# RelayCard_LED_Monitor.net
KiCad netlist of a schematic drawn in Altium Designer
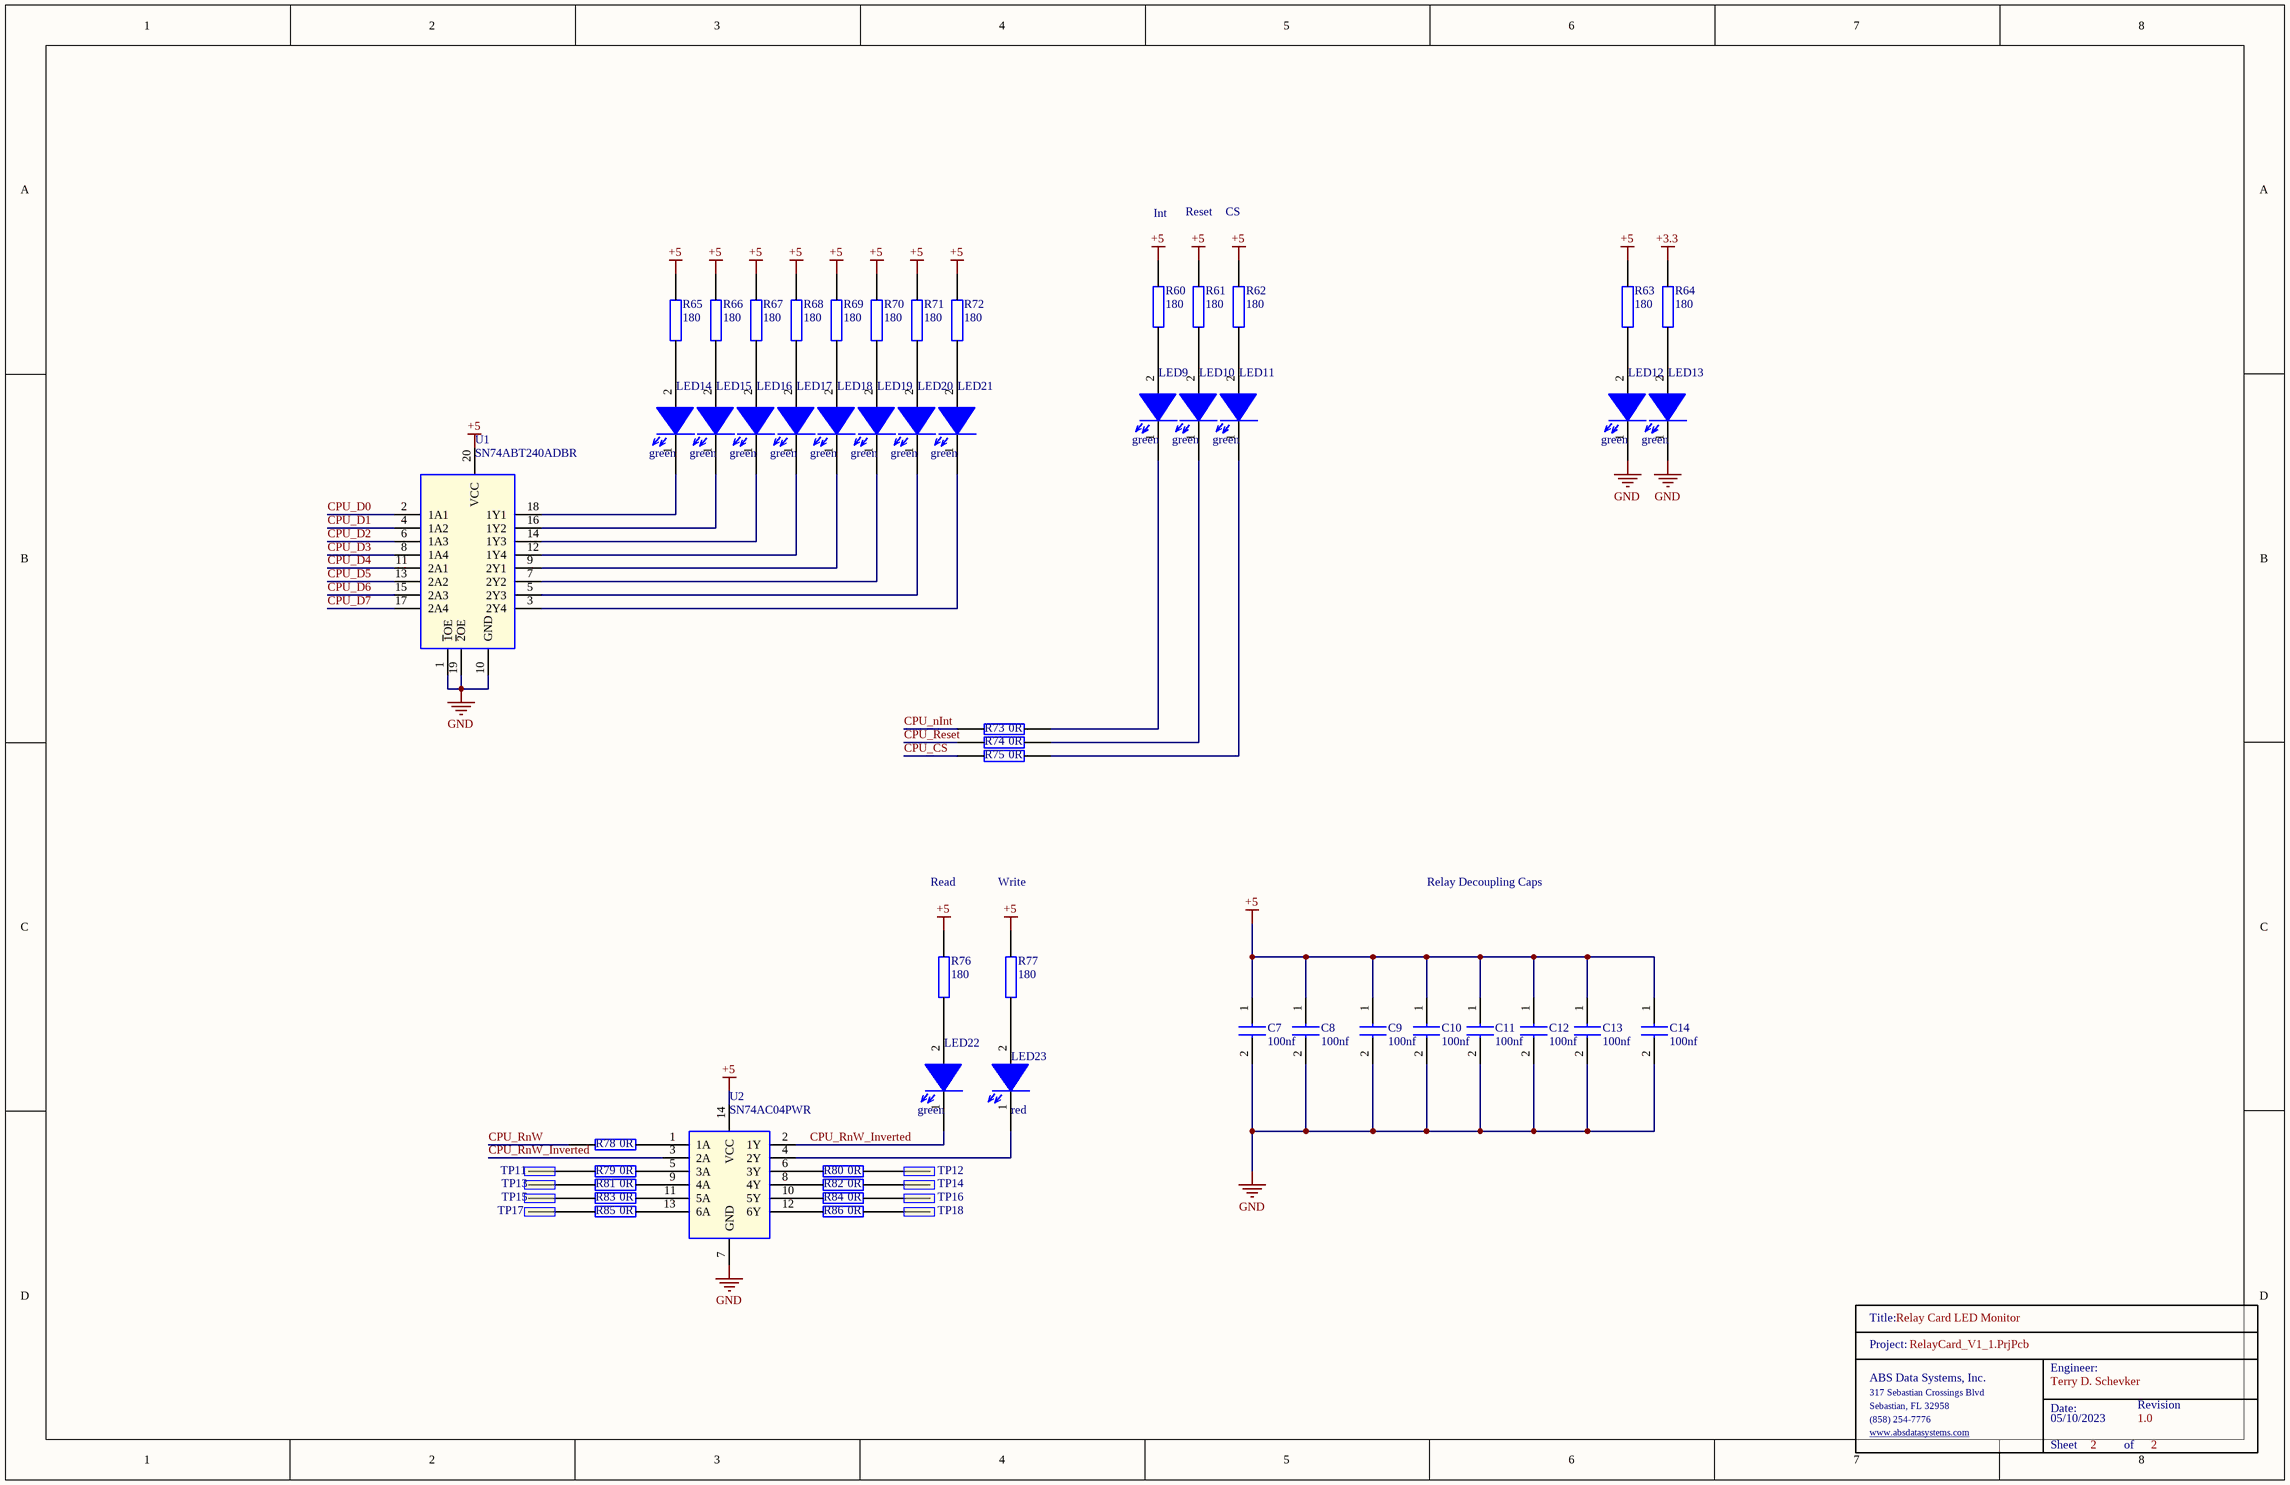
[diagram p0: RelayCard_LED_Monitor.SchDoc]

(export (version "E")
  (design (tool "Eeschema 10.0.6"))
  (components
    (comp (ref "C7")
      (value "100nf")
      (footprint "0603")
      (description "Samsung Electro-Mechanics 0603 100nf")
      (libsource (lib "Capacitors") (part "CL10B104JB8NNNC"))
    )
    (comp (ref "C8")
      (value "100nf")
      (footprint "0603")
      (description "Samsung Electro-Mechanics 0603 100nf")
      (libsource (lib "Capacitors") (part "CL10B104JB8NNNC"))
    )
    (comp (ref "C9")
      (value "100nf")
      (footprint "0603")
      (description "Samsung Electro-Mechanics 0603 100nf")
      (libsource (lib "Capacitors") (part "CL10B104JB8NNNC"))
    )
    (comp (ref "C10")
      (value "100nf")
      (footprint "0603")
      (description "Samsung Electro-Mechanics 0603 100nf")
      (libsource (lib "Capacitors") (part "CL10B104JB8NNNC"))
    )
    (comp (ref "C11")
      (value "100nf")
      (footprint "0603")
      (description "Samsung Electro-Mechanics 0603 100nf")
      (libsource (lib "Capacitors") (part "CL10B104JB8NNNC"))
    )
    (comp (ref "C12")
      (value "100nf")
      (footprint "0603")
      (description "Samsung Electro-Mechanics 0603 100nf")
      (libsource (lib "Capacitors") (part "CL10B104JB8NNNC"))
    )
    (comp (ref "C13")
      (value "100nf")
      (footprint "0603")
      (description "Samsung Electro-Mechanics 0603 100nf")
      (libsource (lib "Capacitors") (part "CL10B104JB8NNNC"))
    )
    (comp (ref "C14")
      (value "100nf")
      (footprint "0603")
      (description "Samsung Electro-Mechanics 0603 100nf")
      (libsource (lib "Capacitors") (part "CL10B104JB8NNNC"))
    )
    (comp (ref "LED9")
      (value "green")
      (footprint "0603_Diode")
      (description "Wurth Elektronik 0603 green")
      (fields
        (field (name "MANUFACTURER") "Wurth Electronics")
        (field (name "MANUFACTURER PART NUMBER") "150060GS75000")
      )
      (libsource (lib "Misc") (part "150060GS75000"))
    )
    (comp (ref "LED10")
      (value "green")
      (footprint "0603_Diode")
      (description "Wurth Elektronik 0603 green")
      (fields
        (field (name "MANUFACTURER") "Wurth Electronics")
        (field (name "MANUFACTURER PART NUMBER") "150060GS75000")
      )
      (libsource (lib "Misc") (part "150060GS75000"))
    )
    (comp (ref "LED11")
      (value "green")
      (footprint "0603_Diode")
      (description "Wurth Elektronik 0603 green")
      (fields
        (field (name "MANUFACTURER") "Wurth Electronics")
        (field (name "MANUFACTURER PART NUMBER") "150060GS75000")
      )
      (libsource (lib "Misc") (part "150060GS75000"))
    )
    (comp (ref "LED12")
      (value "green")
      (footprint "0603_Diode")
      (description "Wurth Elektronik 0603 green")
      (fields
        (field (name "MANUFACTURER") "Wurth Electronics")
        (field (name "MANUFACTURER PART NUMBER") "150060GS75000")
      )
      (libsource (lib "Misc") (part "150060GS75000"))
    )
    (comp (ref "LED13")
      (value "green")
      (footprint "0603_Diode")
      (description "Wurth Elektronik 0603 green")
      (fields
        (field (name "MANUFACTURER") "Wurth Electronics")
        (field (name "MANUFACTURER PART NUMBER") "150060GS75000")
      )
      (libsource (lib "Misc") (part "150060GS75000"))
    )
    (comp (ref "LED14")
      (value "green")
      (footprint "0603_Diode")
      (description "Wurth Elektronik 0603 green")
      (fields
        (field (name "MANUFACTURER") "Wurth Electronics")
        (field (name "MANUFACTURER PART NUMBER") "150060GS75000")
      )
      (libsource (lib "Misc") (part "150060GS75000"))
    )
    (comp (ref "LED15")
      (value "green")
      (footprint "0603_Diode")
      (description "Wurth Elektronik 0603 green")
      (fields
        (field (name "MANUFACTURER") "Wurth Electronics")
        (field (name "MANUFACTURER PART NUMBER") "150060GS75000")
      )
      (libsource (lib "Misc") (part "150060GS75000"))
    )
    (comp (ref "LED16")
      (value "green")
      (footprint "0603_Diode")
      (description "Wurth Elektronik 0603 green")
      (fields
        (field (name "MANUFACTURER") "Wurth Electronics")
        (field (name "MANUFACTURER PART NUMBER") "150060GS75000")
      )
      (libsource (lib "Misc") (part "150060GS75000"))
    )
    (comp (ref "LED17")
      (value "green")
      (footprint "0603_Diode")
      (description "Wurth Elektronik 0603 green")
      (fields
        (field (name "MANUFACTURER") "Wurth Electronics")
        (field (name "MANUFACTURER PART NUMBER") "150060GS75000")
      )
      (libsource (lib "Misc") (part "150060GS75000"))
    )
    (comp (ref "LED18")
      (value "green")
      (footprint "0603_Diode")
      (description "Wurth Elektronik 0603 green")
      (fields
        (field (name "MANUFACTURER") "Wurth Electronics")
        (field (name "MANUFACTURER PART NUMBER") "150060GS75000")
      )
      (libsource (lib "Misc") (part "150060GS75000"))
    )
    (comp (ref "LED19")
      (value "green")
      (footprint "0603_Diode")
      (description "Wurth Elektronik 0603 green")
      (fields
        (field (name "MANUFACTURER") "Wurth Electronics")
        (field (name "MANUFACTURER PART NUMBER") "150060GS75000")
      )
      (libsource (lib "Misc") (part "150060GS75000"))
    )
    (comp (ref "LED20")
      (value "green")
      (footprint "0603_Diode")
      (description "Wurth Elektronik 0603 green")
      (fields
        (field (name "MANUFACTURER") "Wurth Electronics")
        (field (name "MANUFACTURER PART NUMBER") "150060GS75000")
      )
      (libsource (lib "Misc") (part "150060GS75000"))
    )
    (comp (ref "LED21")
      (value "green")
      (footprint "0603_Diode")
      (description "Wurth Elektronik 0603 green")
      (fields
        (field (name "MANUFACTURER") "Wurth Electronics")
        (field (name "MANUFACTURER PART NUMBER") "150060GS75000")
      )
      (libsource (lib "Misc") (part "150060GS75000"))
    )
    (comp (ref "LED22")
      (value "green")
      (footprint "0603_Diode")
      (description "Wurth Elektronik 0603 green")
      (fields
        (field (name "MANUFACTURER") "Wurth Electronics")
        (field (name "MANUFACTURER PART NUMBER") "150060GS75000")
      )
      (libsource (lib "Misc") (part "150060GS75000"))
    )
    (comp (ref "LED23")
      (value "red")
      (footprint "0603_Diode")
      (description "Wurth Elektronik 0603 red")
      (fields
        (field (name "MANUFACTURER") "Wurth Electronics")
        (field (name "MANUFACTURER PART NUMBER") "150060GS75000")
      )
      (libsource (lib "Misc") (part "150060RS75000"))
    )
    (comp (ref "R60")
      (value "180")
      (footprint "0603")
      (description "YAGEO 0603 180 ohm")
      (fields
        (field (name "MOUSER PART NUMBER") "603-RC0603JR-070RL")
        (field (name "MANUFACTURER_PART_NUMBER") "RC0603JR-070RL")
      )
      (libsource (lib "Resistors") (part "RC0603FR-13180RL"))
    )
    (comp (ref "R61")
      (value "180")
      (footprint "0603")
      (description "YAGEO 0603 180 ohm")
      (fields
        (field (name "MOUSER PART NUMBER") "603-RC0603JR-070RL")
        (field (name "MANUFACTURER_PART_NUMBER") "RC0603JR-070RL")
      )
      (libsource (lib "Resistors") (part "RC0603FR-13180RL"))
    )
    (comp (ref "R62")
      (value "180")
      (footprint "0603")
      (description "YAGEO 0603 180 ohm")
      (fields
        (field (name "MOUSER PART NUMBER") "603-RC0603JR-070RL")
        (field (name "MANUFACTURER_PART_NUMBER") "RC0603JR-070RL")
      )
      (libsource (lib "Resistors") (part "RC0603FR-13180RL"))
    )
    (comp (ref "R63")
      (value "180")
      (footprint "0603")
      (description "YAGEO 0603 180 ohm")
      (fields
        (field (name "MOUSER PART NUMBER") "603-RC0603JR-070RL")
        (field (name "MANUFACTURER_PART_NUMBER") "RC0603JR-070RL")
      )
      (libsource (lib "Resistors") (part "RC0603FR-13180RL"))
    )
    (comp (ref "R64")
      (value "180")
      (footprint "0603")
      (description "YAGEO 0603 180 ohm")
      (fields
        (field (name "MOUSER PART NUMBER") "603-RC0603JR-070RL")
        (field (name "MANUFACTURER_PART_NUMBER") "RC0603JR-070RL")
      )
      (libsource (lib "Resistors") (part "RC0603FR-13180RL"))
    )
    (comp (ref "R65")
      (value "180")
      (footprint "0603")
      (description "YAGEO 0603 180 ohm")
      (fields
        (field (name "MOUSER PART NUMBER") "603-RC0603JR-070RL")
        (field (name "MANUFACTURER_PART_NUMBER") "RC0603JR-070RL")
      )
      (libsource (lib "Resistors") (part "RC0603FR-13180RL"))
    )
    (comp (ref "R66")
      (value "180")
      (footprint "0603")
      (description "YAGEO 0603 180 ohm")
      (fields
        (field (name "MOUSER PART NUMBER") "603-RC0603JR-070RL")
        (field (name "MANUFACTURER_PART_NUMBER") "RC0603JR-070RL")
      )
      (libsource (lib "Resistors") (part "RC0603FR-13180RL"))
    )
    (comp (ref "R67")
      (value "180")
      (footprint "0603")
      (description "YAGEO 0603 180 ohm")
      (fields
        (field (name "MOUSER PART NUMBER") "603-RC0603JR-070RL")
        (field (name "MANUFACTURER_PART_NUMBER") "RC0603JR-070RL")
      )
      (libsource (lib "Resistors") (part "RC0603FR-13180RL"))
    )
    (comp (ref "R68")
      (value "180")
      (footprint "0603")
      (description "YAGEO 0603 180 ohm")
      (fields
        (field (name "MOUSER PART NUMBER") "603-RC0603JR-070RL")
        (field (name "MANUFACTURER_PART_NUMBER") "RC0603JR-070RL")
      )
      (libsource (lib "Resistors") (part "RC0603FR-13180RL"))
    )
    (comp (ref "R69")
      (value "180")
      (footprint "0603")
      (description "YAGEO 0603 180 ohm")
      (fields
        (field (name "MOUSER PART NUMBER") "603-RC0603JR-070RL")
        (field (name "MANUFACTURER_PART_NUMBER") "RC0603JR-070RL")
      )
      (libsource (lib "Resistors") (part "RC0603FR-13180RL"))
    )
    (comp (ref "R70")
      (value "180")
      (footprint "0603")
      (description "YAGEO 0603 180 ohm")
      (fields
        (field (name "MOUSER PART NUMBER") "603-RC0603JR-070RL")
        (field (name "MANUFACTURER_PART_NUMBER") "RC0603JR-070RL")
      )
      (libsource (lib "Resistors") (part "RC0603FR-13180RL"))
    )
    (comp (ref "R71")
      (value "180")
      (footprint "0603")
      (description "YAGEO 0603 180 ohm")
      (fields
        (field (name "MOUSER PART NUMBER") "603-RC0603JR-070RL")
        (field (name "MANUFACTURER_PART_NUMBER") "RC0603JR-070RL")
      )
      (libsource (lib "Resistors") (part "RC0603FR-13180RL"))
    )
    (comp (ref "R72")
      (value "180")
      (footprint "0603")
      (description "YAGEO 0603 180 ohm")
      (fields
        (field (name "MOUSER PART NUMBER") "603-RC0603JR-070RL")
        (field (name "MANUFACTURER_PART_NUMBER") "RC0603JR-070RL")
      )
      (libsource (lib "Resistors") (part "RC0603FR-13180RL"))
    )
    (comp (ref "R73")
      (value "0R")
      (footprint "0603")
      (description "YAGEO 0603 0 ohm")
      (fields
        (field (name "MOUSER PART NUMBER") "603-RC0603JR-070RL")
        (field (name "MANUFACTURER_PART_NUMBER") "RC0603JR-070RL")
      )
      (libsource (lib "Resistors") (part "RC0603JR-070RL"))
    )
    (comp (ref "R74")
      (value "0R")
      (footprint "0603")
      (description "YAGEO 0603 0 ohm")
      (fields
        (field (name "MOUSER PART NUMBER") "603-RC0603JR-070RL")
        (field (name "MANUFACTURER_PART_NUMBER") "RC0603JR-070RL")
      )
      (libsource (lib "Resistors") (part "RC0603JR-070RL"))
    )
    (comp (ref "R75")
      (value "0R")
      (footprint "0603")
      (description "YAGEO 0603 0 ohm")
      (fields
        (field (name "MOUSER PART NUMBER") "603-RC0603JR-070RL")
        (field (name "MANUFACTURER_PART_NUMBER") "RC0603JR-070RL")
      )
      (libsource (lib "Resistors") (part "RC0603JR-070RL"))
    )
    (comp (ref "R76")
      (value "180")
      (footprint "0603")
      (description "YAGEO 0603 180 ohm")
      (fields
        (field (name "MOUSER PART NUMBER") "603-RC0603JR-070RL")
        (field (name "MANUFACTURER_PART_NUMBER") "RC0603JR-070RL")
      )
      (libsource (lib "Resistors") (part "RC0603FR-13180RL"))
    )
    (comp (ref "R77")
      (value "180")
      (footprint "0603")
      (description "YAGEO 0603 180 ohm")
      (fields
        (field (name "MOUSER PART NUMBER") "603-RC0603JR-070RL")
        (field (name "MANUFACTURER_PART_NUMBER") "RC0603JR-070RL")
      )
      (libsource (lib "Resistors") (part "RC0603FR-13180RL"))
    )
    (comp (ref "R78")
      (value "0R")
      (footprint "0603")
      (description "YAGEO 0603 0 ohm")
      (fields
        (field (name "MOUSER PART NUMBER") "603-RC0603JR-070RL")
        (field (name "MANUFACTURER_PART_NUMBER") "RC0603JR-070RL")
      )
      (libsource (lib "Resistors") (part "RC0603JR-070RL"))
    )
    (comp (ref "R79")
      (value "0R")
      (footprint "0603")
      (description "YAGEO 0603 0 ohm")
      (fields
        (field (name "MOUSER PART NUMBER") "603-RC0603JR-070RL")
        (field (name "MANUFACTURER_PART_NUMBER") "RC0603JR-070RL")
      )
      (libsource (lib "Resistors") (part "RC0603JR-070RL"))
    )
    (comp (ref "R80")
      (value "0R")
      (footprint "0603")
      (description "YAGEO 0603 0 ohm")
      (fields
        (field (name "MOUSER PART NUMBER") "603-RC0603JR-070RL")
        (field (name "MANUFACTURER_PART_NUMBER") "RC0603JR-070RL")
      )
      (libsource (lib "Resistors") (part "RC0603JR-070RL"))
    )
    (comp (ref "R81")
      (value "0R")
      (footprint "0603")
      (description "YAGEO 0603 0 ohm")
      (fields
        (field (name "MOUSER PART NUMBER") "603-RC0603JR-070RL")
        (field (name "MANUFACTURER_PART_NUMBER") "RC0603JR-070RL")
      )
      (libsource (lib "Resistors") (part "RC0603JR-070RL"))
    )
    (comp (ref "R82")
      (value "0R")
      (footprint "0603")
      (description "YAGEO 0603 0 ohm")
      (fields
        (field (name "MOUSER PART NUMBER") "603-RC0603JR-070RL")
        (field (name "MANUFACTURER_PART_NUMBER") "RC0603JR-070RL")
      )
      (libsource (lib "Resistors") (part "RC0603JR-070RL"))
    )
    (comp (ref "R83")
      (value "0R")
      (footprint "0603")
      (description "YAGEO 0603 0 ohm")
      (fields
        (field (name "MOUSER PART NUMBER") "603-RC0603JR-070RL")
        (field (name "MANUFACTURER_PART_NUMBER") "RC0603JR-070RL")
      )
      (libsource (lib "Resistors") (part "RC0603JR-070RL"))
    )
    (comp (ref "R84")
      (value "0R")
      (footprint "0603")
      (description "YAGEO 0603 0 ohm")
      (fields
        (field (name "MOUSER PART NUMBER") "603-RC0603JR-070RL")
        (field (name "MANUFACTURER_PART_NUMBER") "RC0603JR-070RL")
      )
      (libsource (lib "Resistors") (part "RC0603JR-070RL"))
    )
    (comp (ref "R85")
      (value "0R")
      (footprint "0603")
      (description "YAGEO 0603 0 ohm")
      (fields
        (field (name "MOUSER PART NUMBER") "603-RC0603JR-070RL")
        (field (name "MANUFACTURER_PART_NUMBER") "RC0603JR-070RL")
      )
      (libsource (lib "Resistors") (part "RC0603JR-070RL"))
    )
    (comp (ref "R86")
      (value "0R")
      (footprint "0603")
      (description "YAGEO 0603 0 ohm")
      (fields
        (field (name "MOUSER PART NUMBER") "603-RC0603JR-070RL")
        (field (name "MANUFACTURER_PART_NUMBER") "RC0603JR-070RL")
      )
      (libsource (lib "Resistors") (part "RC0603JR-070RL"))
    )
    (comp (ref "TitleBlock_2") (value "TitleBlock") (libsource (lib "Misc") (part "TitleBlock")))
    (comp (ref "TP11")
      (value "TP")
      (footprint "TP")
      (fields
        (field (name "MANUFACTURER") "Samtec")
        (field (name "MANUFACTURER PART NUMBER") "TST-105-01-G-D")
      )
      (libsource (lib "") (part "TP_1"))
    )
    (comp (ref "TP12")
      (value "TP")
      (footprint "TP")
      (fields
        (field (name "MANUFACTURER") "Samtec")
        (field (name "MANUFACTURER PART NUMBER") "TST-105-01-G-D")
      )
      (libsource (lib "Misc") (part "TP"))
    )
    (comp (ref "TP13")
      (value "TP")
      (footprint "TP")
      (fields
        (field (name "MANUFACTURER") "Samtec")
        (field (name "MANUFACTURER PART NUMBER") "TST-105-01-G-D")
      )
      (libsource (lib "") (part "TP_1"))
    )
    (comp (ref "TP14")
      (value "TP")
      (footprint "TP")
      (fields
        (field (name "MANUFACTURER") "Samtec")
        (field (name "MANUFACTURER PART NUMBER") "TST-105-01-G-D")
      )
      (libsource (lib "Misc") (part "TP"))
    )
    (comp (ref "TP15")
      (value "TP")
      (footprint "TP")
      (fields
        (field (name "MANUFACTURER") "Samtec")
        (field (name "MANUFACTURER PART NUMBER") "TST-105-01-G-D")
      )
      (libsource (lib "") (part "TP_1"))
    )
    (comp (ref "TP16")
      (value "TP")
      (footprint "TP")
      (fields
        (field (name "MANUFACTURER") "Samtec")
        (field (name "MANUFACTURER PART NUMBER") "TST-105-01-G-D")
      )
      (libsource (lib "Misc") (part "TP"))
    )
    (comp (ref "TP17")
      (value "TP")
      (footprint "TP")
      (fields
        (field (name "MANUFACTURER") "Samtec")
        (field (name "MANUFACTURER PART NUMBER") "TST-105-01-G-D")
      )
      (libsource (lib "") (part "TP_1"))
    )
    (comp (ref "TP18")
      (value "TP")
      (footprint "TP")
      (fields
        (field (name "MANUFACTURER") "Samtec")
        (field (name "MANUFACTURER PART NUMBER") "TST-105-01-G-D")
      )
      (libsource (lib "Misc") (part "TP"))
    )
    (comp (ref "U1")
      (value "SN74ABT240ADBR")
      (footprint "SOP65P780X200-20N")
      (description "Octal Buffers/Drivers With 3-State Outputs")
      (fields (field (name "MOUSER PART NUMBER") "595-SN74ABT240ADBR"))
      (libsource (lib "Logic") (part "SN74ABT240ADBR"))
    )
    (comp (ref "U2")
      (value "SN74AC04PWR")
      (footprint "SOP65P640X120-14N")
      (description "Hex Inverters")
      (fields (field (name "MOUSER PART NUMBER") "595-SN74AC04PWR"))
      (libsource (lib "Logic") (part "SN74AC04PWR"))
    )
  )
  (nets
    (net (code "1") (name "+3.3") (class "Default")
      (node (ref "R64") (pin "2") (pinfunction "2_2") (pintype "passive"))
    )
    (net (code "2") (name "+5") (class "Default")
      (node (ref "C10") (pin "1") (pinfunction "1_1") (pintype "passive"))
      (node (ref "C11") (pin "1") (pinfunction "1_1") (pintype "passive"))
      (node (ref "C12") (pin "1") (pinfunction "1_1") (pintype "passive"))
      (node (ref "C13") (pin "1") (pinfunction "1_1") (pintype "passive"))
      (node (ref "C14") (pin "1") (pinfunction "1_1") (pintype "passive"))
      (node (ref "C7") (pin "1") (pinfunction "1_1") (pintype "passive"))
      (node (ref "C8") (pin "1") (pinfunction "1_1") (pintype "passive"))
      (node (ref "C9") (pin "1") (pinfunction "1_1") (pintype "passive"))
      (node (ref "R60") (pin "2") (pinfunction "2_2") (pintype "passive"))
      (node (ref "R61") (pin "2") (pinfunction "2_2") (pintype "passive"))
      (node (ref "R62") (pin "2") (pinfunction "2_2") (pintype "passive"))
      (node (ref "R63") (pin "2") (pinfunction "2_2") (pintype "passive"))
      (node (ref "R65") (pin "2") (pinfunction "2_2") (pintype "passive"))
      (node (ref "R66") (pin "2") (pinfunction "2_2") (pintype "passive"))
      (node (ref "R67") (pin "2") (pinfunction "2_2") (pintype "passive"))
      (node (ref "R68") (pin "2") (pinfunction "2_2") (pintype "passive"))
      (node (ref "R69") (pin "2") (pinfunction "2_2") (pintype "passive"))
      (node (ref "R70") (pin "2") (pinfunction "2_2") (pintype "passive"))
      (node (ref "R71") (pin "2") (pinfunction "2_2") (pintype "passive"))
      (node (ref "R72") (pin "2") (pinfunction "2_2") (pintype "passive"))
      (node (ref "R76") (pin "2") (pinfunction "2_2") (pintype "passive"))
      (node (ref "R77") (pin "2") (pinfunction "2_2") (pintype "passive"))
      (node (ref "U1") (pin "20") (pinfunction "VCC_20") (pintype "passive"))
      (node (ref "U2") (pin "14") (pinfunction "VCC_14") (pintype "passive"))
    )
    (net (code "3") (name "/CPU_CS") (class "Default")
      (node (ref "R75") (pin "1") (pinfunction "1_1") (pintype "passive"))
    )
    (net (code "4") (name "/CPU_D0") (class "Default")
      (node (ref "U1") (pin "2") (pinfunction "1A1_2") (pintype "passive"))
    )
    (net (code "5") (name "/CPU_D1") (class "Default")
      (node (ref "U1") (pin "4") (pinfunction "1A2_4") (pintype "passive"))
    )
    (net (code "6") (name "/CPU_D2") (class "Default")
      (node (ref "U1") (pin "6") (pinfunction "1A3_6") (pintype "passive"))
    )
    (net (code "7") (name "/CPU_D3") (class "Default")
      (node (ref "U1") (pin "8") (pinfunction "1A4_8") (pintype "passive"))
    )
    (net (code "8") (name "/CPU_D4") (class "Default")
      (node (ref "U1") (pin "11") (pinfunction "2A1_11") (pintype "passive"))
    )
    (net (code "9") (name "/CPU_D5") (class "Default")
      (node (ref "U1") (pin "13") (pinfunction "2A2_13") (pintype "passive"))
    )
    (net (code "10") (name "/CPU_D6") (class "Default")
      (node (ref "U1") (pin "15") (pinfunction "2A3_15") (pintype "passive"))
    )
    (net (code "11") (name "/CPU_D7") (class "Default")
      (node (ref "U1") (pin "17") (pinfunction "2A4_17") (pintype "passive"))
    )
    (net (code "12") (name "/CPU_Reset") (class "Default")
      (node (ref "R74") (pin "1") (pinfunction "1_1") (pintype "passive"))
    )
    (net (code "13") (name "/CPU_RnW") (class "Default")
      (node (ref "R78") (pin "1") (pinfunction "1_1") (pintype "passive"))
    )
    (net (code "14") (name "/CPU_RnW_Inverted") (class "Default")
      (node (ref "LED22") (pin "1") (pinfunction "K_1") (pintype "passive"))
      (node (ref "U2") (pin "2") (pinfunction "1Y_2") (pintype "passive"))
      (node (ref "U2") (pin "3") (pinfunction "2A_3") (pintype "passive"))
    )
    (net (code "15") (name "/CPU_nInt") (class "Default")
      (node (ref "R73") (pin "1") (pinfunction "1_1") (pintype "passive"))
    )
    (net (code "16") (name "GND") (class "Default")
      (node (ref "C10") (pin "2") (pinfunction "2_2") (pintype "passive"))
      (node (ref "C11") (pin "2") (pinfunction "2_2") (pintype "passive"))
      (node (ref "C12") (pin "2") (pinfunction "2_2") (pintype "passive"))
      (node (ref "C13") (pin "2") (pinfunction "2_2") (pintype "passive"))
      (node (ref "C14") (pin "2") (pinfunction "2_2") (pintype "passive"))
      (node (ref "C7") (pin "2") (pinfunction "2_2") (pintype "passive"))
      (node (ref "C8") (pin "2") (pinfunction "2_2") (pintype "passive"))
      (node (ref "C9") (pin "2") (pinfunction "2_2") (pintype "passive"))
      (node (ref "LED12") (pin "1") (pinfunction "K_1") (pintype "passive"))
      (node (ref "LED13") (pin "1") (pinfunction "K_1") (pintype "passive"))
      (node (ref "U1") (pin "1") (pinfunction "~{1}OE_1") (pintype "passive"))
      (node (ref "U1") (pin "10") (pinfunction "GND_10") (pintype "passive"))
      (node (ref "U1") (pin "19") (pinfunction "~{2}OE_19") (pintype "passive"))
      (node (ref "U2") (pin "7") (pinfunction "GND_7") (pintype "passive"))
    )
    (net (code "17") (name "Net-(LED9-A)") (class "Default")
      (node (ref "LED9") (pin "2") (pinfunction "A_2") (pintype "passive"))
      (node (ref "R60") (pin "1") (pinfunction "1_1") (pintype "passive"))
    )
    (net (code "18") (name "Net-(LED9-K)") (class "Default")
      (node (ref "LED9") (pin "1") (pinfunction "K_1") (pintype "passive"))
      (node (ref "R73") (pin "2") (pinfunction "2_2") (pintype "passive"))
    )
    (net (code "19") (name "Net-(LED10-A)") (class "Default")
      (node (ref "LED10") (pin "2") (pinfunction "A_2") (pintype "passive"))
      (node (ref "R61") (pin "1") (pinfunction "1_1") (pintype "passive"))
    )
    (net (code "20") (name "Net-(LED10-K)") (class "Default")
      (node (ref "LED10") (pin "1") (pinfunction "K_1") (pintype "passive"))
      (node (ref "R74") (pin "2") (pinfunction "2_2") (pintype "passive"))
    )
    (net (code "21") (name "Net-(LED11-A)") (class "Default")
      (node (ref "LED11") (pin "2") (pinfunction "A_2") (pintype "passive"))
      (node (ref "R62") (pin "1") (pinfunction "1_1") (pintype "passive"))
    )
    (net (code "22") (name "Net-(LED11-K)") (class "Default")
      (node (ref "LED11") (pin "1") (pinfunction "K_1") (pintype "passive"))
      (node (ref "R75") (pin "2") (pinfunction "2_2") (pintype "passive"))
    )
    (net (code "23") (name "Net-(LED12-A)") (class "Default")
      (node (ref "LED12") (pin "2") (pinfunction "A_2") (pintype "passive"))
      (node (ref "R63") (pin "1") (pinfunction "1_1") (pintype "passive"))
    )
    (net (code "24") (name "Net-(LED13-A)") (class "Default")
      (node (ref "LED13") (pin "2") (pinfunction "A_2") (pintype "passive"))
      (node (ref "R64") (pin "1") (pinfunction "1_1") (pintype "passive"))
    )
    (net (code "25") (name "Net-(LED14-A)") (class "Default")
      (node (ref "LED14") (pin "2") (pinfunction "A_2") (pintype "passive"))
      (node (ref "R65") (pin "1") (pinfunction "1_1") (pintype "passive"))
    )
    (net (code "26") (name "Net-(LED14-K)") (class "Default")
      (node (ref "LED14") (pin "1") (pinfunction "K_1") (pintype "passive"))
      (node (ref "U1") (pin "18") (pinfunction "1Y1_18") (pintype "passive"))
    )
    (net (code "27") (name "Net-(LED15-A)") (class "Default")
      (node (ref "LED15") (pin "2") (pinfunction "A_2") (pintype "passive"))
      (node (ref "R66") (pin "1") (pinfunction "1_1") (pintype "passive"))
    )
    (net (code "28") (name "Net-(LED15-K)") (class "Default")
      (node (ref "LED15") (pin "1") (pinfunction "K_1") (pintype "passive"))
      (node (ref "U1") (pin "16") (pinfunction "1Y2_16") (pintype "passive"))
    )
    (net (code "29") (name "Net-(LED16-A)") (class "Default")
      (node (ref "LED16") (pin "2") (pinfunction "A_2") (pintype "passive"))
      (node (ref "R67") (pin "1") (pinfunction "1_1") (pintype "passive"))
    )
    (net (code "30") (name "Net-(LED16-K)") (class "Default")
      (node (ref "LED16") (pin "1") (pinfunction "K_1") (pintype "passive"))
      (node (ref "U1") (pin "14") (pinfunction "1Y3_14") (pintype "passive"))
    )
    (net (code "31") (name "Net-(LED17-A)") (class "Default")
      (node (ref "LED17") (pin "2") (pinfunction "A_2") (pintype "passive"))
      (node (ref "R68") (pin "1") (pinfunction "1_1") (pintype "passive"))
    )
    (net (code "32") (name "Net-(LED17-K)") (class "Default")
      (node (ref "LED17") (pin "1") (pinfunction "K_1") (pintype "passive"))
      (node (ref "U1") (pin "12") (pinfunction "1Y4_12") (pintype "passive"))
    )
    (net (code "33") (name "Net-(LED18-A)") (class "Default")
      (node (ref "LED18") (pin "2") (pinfunction "A_2") (pintype "passive"))
      (node (ref "R69") (pin "1") (pinfunction "1_1") (pintype "passive"))
    )
    (net (code "34") (name "Net-(LED18-K)") (class "Default")
      (node (ref "LED18") (pin "1") (pinfunction "K_1") (pintype "passive"))
      (node (ref "U1") (pin "9") (pinfunction "2Y1_9") (pintype "passive"))
    )
    (net (code "35") (name "Net-(LED19-A)") (class "Default")
      (node (ref "LED19") (pin "2") (pinfunction "A_2") (pintype "passive"))
      (node (ref "R70") (pin "1") (pinfunction "1_1") (pintype "passive"))
    )
    (net (code "36") (name "Net-(LED19-K)") (class "Default")
      (node (ref "LED19") (pin "1") (pinfunction "K_1") (pintype "passive"))
      (node (ref "U1") (pin "7") (pinfunction "2Y2_7") (pintype "passive"))
    )
    (net (code "37") (name "Net-(LED20-A)") (class "Default")
      (node (ref "LED20") (pin "2") (pinfunction "A_2") (pintype "passive"))
      (node (ref "R71") (pin "1") (pinfunction "1_1") (pintype "passive"))
    )
    (net (code "38") (name "Net-(LED20-K)") (class "Default")
      (node (ref "LED20") (pin "1") (pinfunction "K_1") (pintype "passive"))
      (node (ref "U1") (pin "5") (pinfunction "2Y3_5") (pintype "passive"))
    )
    (net (code "39") (name "Net-(LED21-A)") (class "Default")
      (node (ref "LED21") (pin "2") (pinfunction "A_2") (pintype "passive"))
      (node (ref "R72") (pin "1") (pinfunction "1_1") (pintype "passive"))
    )
    (net (code "40") (name "Net-(LED21-K)") (class "Default")
      (node (ref "LED21") (pin "1") (pinfunction "K_1") (pintype "passive"))
      (node (ref "U1") (pin "3") (pinfunction "2Y4_3") (pintype "passive"))
    )
    (net (code "41") (name "Net-(LED22-A)") (class "Default")
      (node (ref "LED22") (pin "2") (pinfunction "A_2") (pintype "passive"))
      (node (ref "R76") (pin "1") (pinfunction "1_1") (pintype "passive"))
    )
    (net (code "42") (name "Net-(LED23-A)") (class "Default")
      (node (ref "LED23") (pin "2") (pinfunction "A_2") (pintype "passive"))
      (node (ref "R77") (pin "1") (pinfunction "1_1") (pintype "passive"))
    )
    (net (code "43") (name "Net-(LED23-K)") (class "Default")
      (node (ref "LED23") (pin "1") (pinfunction "K_1") (pintype "passive"))
      (node (ref "U2") (pin "4") (pinfunction "2Y_4") (pintype "passive"))
    )
    (net (code "44") (name "Net-(R79-Pad1)") (class "Default")
      (node (ref "R79") (pin "1") (pinfunction "1_1") (pintype "passive"))
      (node (ref "TP11") (pin "1") (pinfunction "1_1") (pintype "passive"))
    )
    (net (code "45") (name "Net-(R80-Pad2)") (class "Default")
      (node (ref "R80") (pin "2") (pinfunction "2_2") (pintype "passive"))
      (node (ref "TP12") (pin "1") (pinfunction "1_1") (pintype "passive"))
    )
    (net (code "46") (name "Net-(R81-Pad1)") (class "Default")
      (node (ref "R81") (pin "1") (pinfunction "1_1") (pintype "passive"))
      (node (ref "TP13") (pin "1") (pinfunction "1_1") (pintype "passive"))
    )
    (net (code "47") (name "Net-(R82-Pad2)") (class "Default")
      (node (ref "R82") (pin "2") (pinfunction "2_2") (pintype "passive"))
      (node (ref "TP14") (pin "1") (pinfunction "1_1") (pintype "passive"))
    )
    (net (code "48") (name "Net-(R83-Pad1)") (class "Default")
      (node (ref "R83") (pin "1") (pinfunction "1_1") (pintype "passive"))
      (node (ref "TP15") (pin "1") (pinfunction "1_1") (pintype "passive"))
    )
    (net (code "49") (name "Net-(R84-Pad2)") (class "Default")
      (node (ref "R84") (pin "2") (pinfunction "2_2") (pintype "passive"))
      (node (ref "TP16") (pin "1") (pinfunction "1_1") (pintype "passive"))
    )
    (net (code "50") (name "Net-(R85-Pad1)") (class "Default")
      (node (ref "R85") (pin "1") (pinfunction "1_1") (pintype "passive"))
      (node (ref "TP17") (pin "1") (pinfunction "1_1") (pintype "passive"))
    )
    (net (code "51") (name "Net-(R86-Pad2)") (class "Default")
      (node (ref "R86") (pin "2") (pinfunction "2_2") (pintype "passive"))
      (node (ref "TP18") (pin "1") (pinfunction "1_1") (pintype "passive"))
    )
    (net (code "52") (name "Net-(U2-1A)") (class "Default")
      (node (ref "R78") (pin "2") (pinfunction "2_2") (pintype "passive"))
      (node (ref "U2") (pin "1") (pinfunction "1A_1") (pintype "passive"))
    )
    (net (code "53") (name "Net-(U2-3A)") (class "Default")
      (node (ref "R79") (pin "2") (pinfunction "2_2") (pintype "passive"))
      (node (ref "U2") (pin "5") (pinfunction "3A_5") (pintype "passive"))
    )
    (net (code "54") (name "Net-(U2-3Y)") (class "Default")
      (node (ref "R80") (pin "1") (pinfunction "1_1") (pintype "passive"))
      (node (ref "U2") (pin "6") (pinfunction "3Y_6") (pintype "passive"))
    )
    (net (code "55") (name "Net-(U2-4A)") (class "Default")
      (node (ref "R81") (pin "2") (pinfunction "2_2") (pintype "passive"))
      (node (ref "U2") (pin "9") (pinfunction "4A_9") (pintype "passive"))
    )
    (net (code "56") (name "Net-(U2-4Y)") (class "Default")
      (node (ref "R82") (pin "1") (pinfunction "1_1") (pintype "passive"))
      (node (ref "U2") (pin "8") (pinfunction "4Y_8") (pintype "passive"))
    )
    (net (code "57") (name "Net-(U2-5A)") (class "Default")
      (node (ref "R83") (pin "2") (pinfunction "2_2") (pintype "passive"))
      (node (ref "U2") (pin "11") (pinfunction "5A_11") (pintype "passive"))
    )
    (net (code "58") (name "Net-(U2-5Y)") (class "Default")
      (node (ref "R84") (pin "1") (pinfunction "1_1") (pintype "passive"))
      (node (ref "U2") (pin "10") (pinfunction "5Y_10") (pintype "passive"))
    )
    (net (code "59") (name "Net-(U2-6A)") (class "Default")
      (node (ref "R85") (pin "2") (pinfunction "2_2") (pintype "passive"))
      (node (ref "U2") (pin "13") (pinfunction "6A_13") (pintype "passive"))
    )
    (net (code "60") (name "Net-(U2-6Y)") (class "Default")
      (node (ref "R86") (pin "1") (pinfunction "1_1") (pintype "passive"))
      (node (ref "U2") (pin "12") (pinfunction "6Y_12") (pintype "passive"))
    )
  )
)
